# Main.net
KiCad netlist of a schematic drawn in Altium Designer
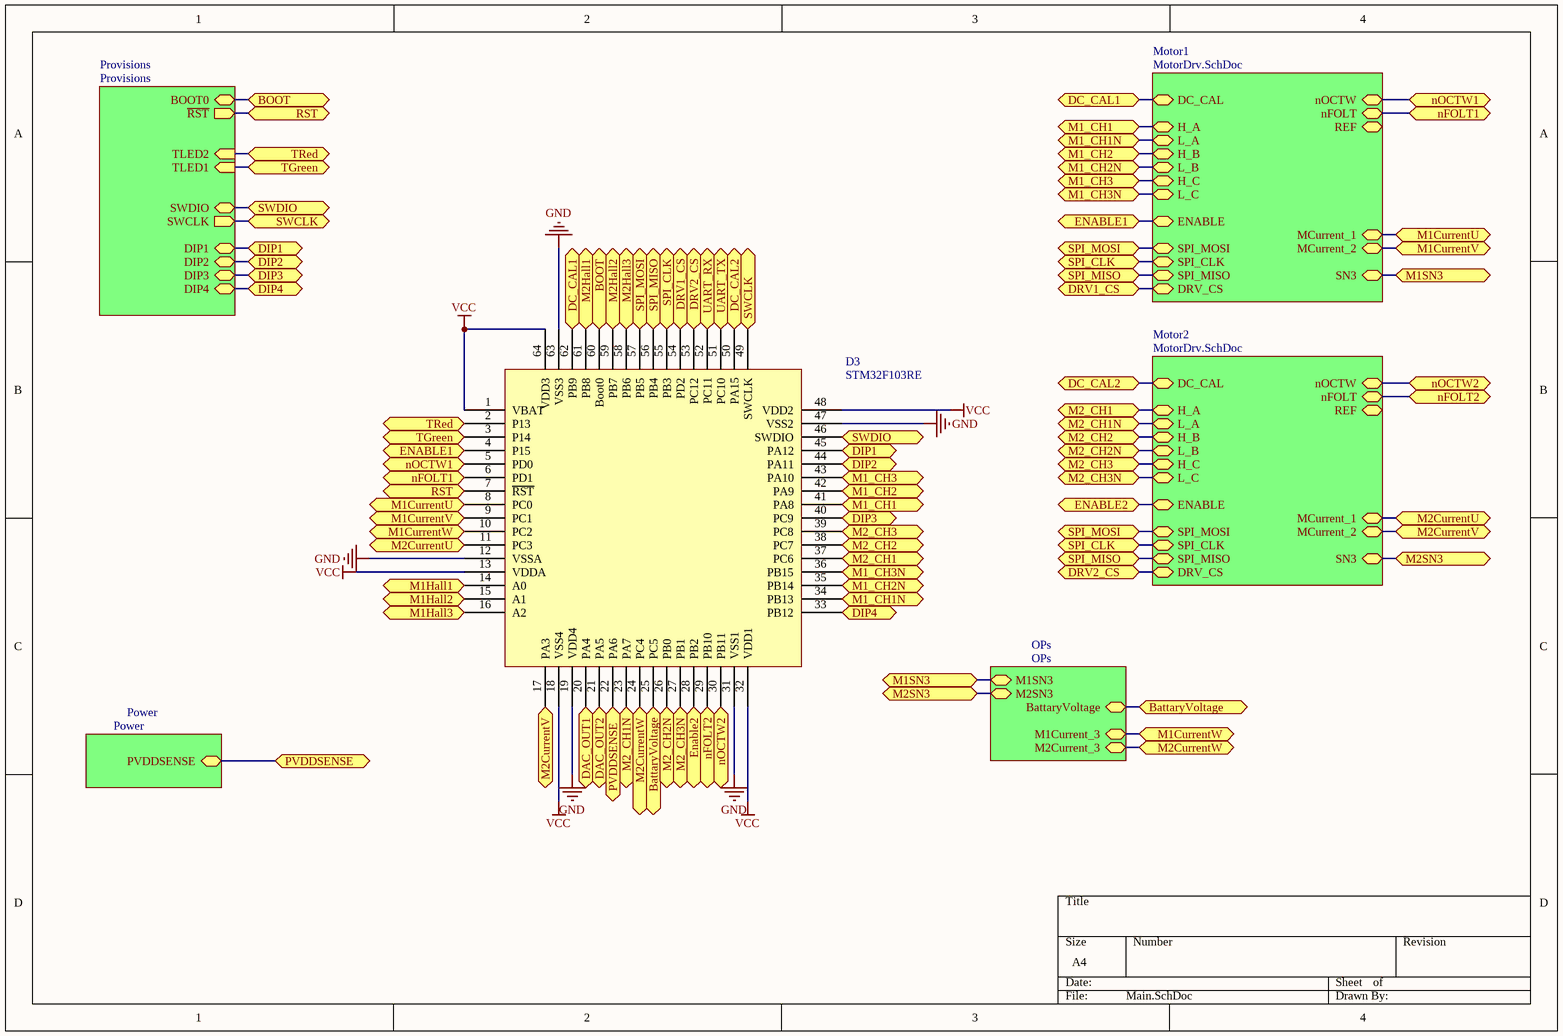
[diagram p0: Main.SchDoc]

(export (version "E")
  (design (tool "Eeschema 10.0.6"))
  (components
    (comp (ref "D3")
      (value "STM32F103RE")
      (footprint "LQFP64_N")
      (libsource (lib "STRobot") (part "STM32F103RE"))
    )
  )
  (nets
    (net (code "1") (name "/BOOT") (class "Default")
      (node (ref "D3") (pin "60") (pinfunction "Boot0_60") (pintype "passive"))
    )
    (net (code "2") (name "/BattaryVoltage") (class "Default")
      (node (ref "D3") (pin "25") (pinfunction "PC5_25") (pintype "passive"))
    )
    (net (code "3") (name "/DAC_OUT1") (class "Default")
      (node (ref "D3") (pin "20") (pinfunction "PA4_20") (pintype "passive"))
    )
    (net (code "4") (name "/DAC_OUT2") (class "Default")
      (node (ref "D3") (pin "21") (pinfunction "PA5_21") (pintype "passive"))
    )
    (net (code "5") (name "/DC_CAL1") (class "Default")
      (node (ref "D3") (pin "62") (pinfunction "PB9_62") (pintype "passive"))
    )
    (net (code "6") (name "/DC_CAL2") (class "Default")
      (node (ref "D3") (pin "50") (pinfunction "PA15_50") (pintype "passive"))
    )
    (net (code "7") (name "/DIP1") (class "Default")
      (node (ref "D3") (pin "45") (pinfunction "PA12_45") (pintype "passive"))
    )
    (net (code "8") (name "/DIP2") (class "Default")
      (node (ref "D3") (pin "44") (pinfunction "PA11_44") (pintype "passive"))
    )
    (net (code "9") (name "/DIP3") (class "Default")
      (node (ref "D3") (pin "40") (pinfunction "PC9_40") (pintype "passive"))
    )
    (net (code "10") (name "/DIP4") (class "Default")
      (node (ref "D3") (pin "33") (pinfunction "PB12_33") (pintype "power_in"))
    )
    (net (code "11") (name "/DRV1_CS") (class "Default")
      (node (ref "D3") (pin "54") (pinfunction "PD2_54") (pintype "passive"))
    )
    (net (code "12") (name "/DRV2_CS") (class "Default")
      (node (ref "D3") (pin "53") (pinfunction "PC12_53") (pintype "passive"))
    )
    (net (code "13") (name "/ENABLE1") (class "Default")
      (node (ref "D3") (pin "4") (pinfunction "P15_4") (pintype "passive"))
    )
    (net (code "15") (name "/Enable2") (class "Default")
      (node (ref "D3") (pin "28") (pinfunction "PB2_28") (pintype "passive"))
    )
    (net (code "16") (name "/M1CurrentU") (class "Default")
      (node (ref "D3") (pin "8") (pinfunction "PC0_8") (pintype "passive"))
    )
    (net (code "17") (name "/M1CurrentV") (class "Default")
      (node (ref "D3") (pin "9") (pinfunction "PC1_9") (pintype "passive"))
    )
    (net (code "18") (name "/M1CurrentW") (class "Default")
      (node (ref "D3") (pin "10") (pinfunction "PC2_10") (pintype "passive"))
    )
    (net (code "19") (name "/M1Hall1") (class "Default")
      (node (ref "D3") (pin "14") (pinfunction "A0_14") (pintype "passive"))
    )
    (net (code "20") (name "/M1Hall2") (class "Default")
      (node (ref "D3") (pin "15") (pinfunction "A1_15") (pintype "passive"))
    )
    (net (code "21") (name "/M1Hall3") (class "Default")
      (node (ref "D3") (pin "16") (pinfunction "A2_16") (pintype "passive"))
    )
    (net (code "23") (name "/M1_CH1") (class "Default")
      (node (ref "D3") (pin "41") (pinfunction "PA8_41") (pintype "passive"))
    )
    (net (code "24") (name "/M1_CH1N") (class "Default")
      (node (ref "D3") (pin "34") (pinfunction "PB13_34") (pintype "passive"))
    )
    (net (code "25") (name "/M1_CH2") (class "Default")
      (node (ref "D3") (pin "42") (pinfunction "PA9_42") (pintype "passive"))
    )
    (net (code "26") (name "/M1_CH2N") (class "Default")
      (node (ref "D3") (pin "35") (pinfunction "PB14_35") (pintype "passive"))
    )
    (net (code "27") (name "/M1_CH3") (class "Default")
      (node (ref "D3") (pin "43") (pinfunction "PA10_43") (pintype "passive"))
    )
    (net (code "28") (name "/M1_CH3N") (class "Default")
      (node (ref "D3") (pin "36") (pinfunction "PB15_36") (pintype "passive"))
    )
    (net (code "29") (name "/M2CurrentU") (class "Default")
      (node (ref "D3") (pin "11") (pinfunction "PC3_11") (pintype "passive"))
    )
    (net (code "30") (name "/M2CurrentV") (class "Default")
      (node (ref "D3") (pin "17") (pinfunction "PA3_17") (pintype "power_in"))
    )
    (net (code "31") (name "/M2CurrentW") (class "Default")
      (node (ref "D3") (pin "24") (pinfunction "PC4_24") (pintype "passive"))
    )
    (net (code "32") (name "/M2Hall1") (class "Default")
      (node (ref "D3") (pin "61") (pinfunction "PB8_61") (pintype "passive"))
    )
    (net (code "33") (name "/M2Hall2") (class "Default")
      (node (ref "D3") (pin "59") (pinfunction "PB7_59") (pintype "passive"))
    )
    (net (code "34") (name "/M2Hall3") (class "Default")
      (node (ref "D3") (pin "58") (pinfunction "PB6_58") (pintype "passive"))
    )
    (net (code "36") (name "/M2_CH1") (class "Default")
      (node (ref "D3") (pin "37") (pinfunction "PC6_37") (pintype "passive"))
    )
    (net (code "37") (name "/M2_CH1N") (class "Default")
      (node (ref "D3") (pin "23") (pinfunction "PA7_23") (pintype "passive"))
    )
    (net (code "38") (name "/M2_CH2") (class "Default")
      (node (ref "D3") (pin "38") (pinfunction "PC7_38") (pintype "passive"))
    )
    (net (code "39") (name "/M2_CH2N") (class "Default")
      (node (ref "D3") (pin "26") (pinfunction "PB0_26") (pintype "passive"))
    )
    (net (code "40") (name "/M2_CH3") (class "Default")
      (node (ref "D3") (pin "39") (pinfunction "PC8_39") (pintype "passive"))
    )
    (net (code "41") (name "/M2_CH3N") (class "Default")
      (node (ref "D3") (pin "27") (pinfunction "PB1_27") (pintype "passive"))
    )
    (net (code "42") (name "/PVDDSENSE") (class "Default")
      (node (ref "D3") (pin "22") (pinfunction "PA6_22") (pintype "passive"))
    )
    (net (code "45") (name "/RST") (class "Default")
      (node (ref "D3") (pin "7") (pinfunction "~{RST}_7") (pintype "passive"))
    )
    (net (code "46") (name "/SPI_CLK") (class "Default")
      (node (ref "D3") (pin "55") (pinfunction "PB3_55") (pintype "passive"))
    )
    (net (code "47") (name "/SPI_MISO") (class "Default")
      (node (ref "D3") (pin "56") (pinfunction "PB4_56") (pintype "passive"))
    )
    (net (code "48") (name "/SPI_MOSI") (class "Default")
      (node (ref "D3") (pin "57") (pinfunction "PB5_57") (pintype "passive"))
    )
    (net (code "49") (name "/SWCLK") (class "Default")
      (node (ref "D3") (pin "49") (pinfunction "SWCLK_49") (pintype "passive"))
    )
    (net (code "50") (name "/SWDIO") (class "Default")
      (node (ref "D3") (pin "46") (pinfunction "SWDIO_46") (pintype "passive"))
    )
    (net (code "51") (name "/TGreen") (class "Default")
      (node (ref "D3") (pin "3") (pinfunction "P14_3") (pintype "passive"))
    )
    (net (code "52") (name "/TRed") (class "Default")
      (node (ref "D3") (pin "2") (pinfunction "P13_2") (pintype "passive"))
    )
    (net (code "53") (name "/UART_RX") (class "Default")
      (node (ref "D3") (pin "52") (pinfunction "PC11_52") (pintype "passive"))
    )
    (net (code "54") (name "/UART_TX") (class "Default")
      (node (ref "D3") (pin "51") (pinfunction "PC10_51") (pintype "passive"))
    )
    (net (code "55") (name "/nFOLT1") (class "Default")
      (node (ref "D3") (pin "6") (pinfunction "PD1_6") (pintype "passive"))
    )
    (net (code "56") (name "/nFOLT2") (class "Default")
      (node (ref "D3") (pin "29") (pinfunction "PB10_29") (pintype "passive"))
    )
    (net (code "57") (name "/nOCTW1") (class "Default")
      (node (ref "D3") (pin "5") (pinfunction "PD0_5") (pintype "passive"))
    )
    (net (code "58") (name "/nOCTW2") (class "Default")
      (node (ref "D3") (pin "30") (pinfunction "PB11_30") (pintype "passive"))
    )
    (net (code "59") (name "GND") (class "Default")
      (node (ref "D3") (pin "12") (pinfunction "VSSA_12") (pintype "passive"))
      (node (ref "D3") (pin "19") (pinfunction "VDD4_19") (pintype "passive"))
      (node (ref "D3") (pin "31") (pinfunction "VSS1_31") (pintype "passive"))
      (node (ref "D3") (pin "47") (pinfunction "VSS2_47") (pintype "power_in"))
      (node (ref "D3") (pin "63") (pinfunction "VSS3_63") (pintype "passive"))
    )
    (net (code "60") (name "VCC") (class "Default")
      (node (ref "D3") (pin "1") (pinfunction "VBAT_1") (pintype "power_in"))
      (node (ref "D3") (pin "13") (pinfunction "VDDA_13") (pintype "passive"))
      (node (ref "D3") (pin "18") (pinfunction "VSS4_18") (pintype "passive"))
      (node (ref "D3") (pin "32") (pinfunction "VDD1_32") (pintype "passive"))
      (node (ref "D3") (pin "48") (pinfunction "VDD2_48") (pintype "passive"))
      (node (ref "D3") (pin "64") (pinfunction "VDD3_64") (pintype "passive"))
    )
  )
)
